# RS485_tranceiver.net
KiCad netlist of a schematic drawn in Altium Designer
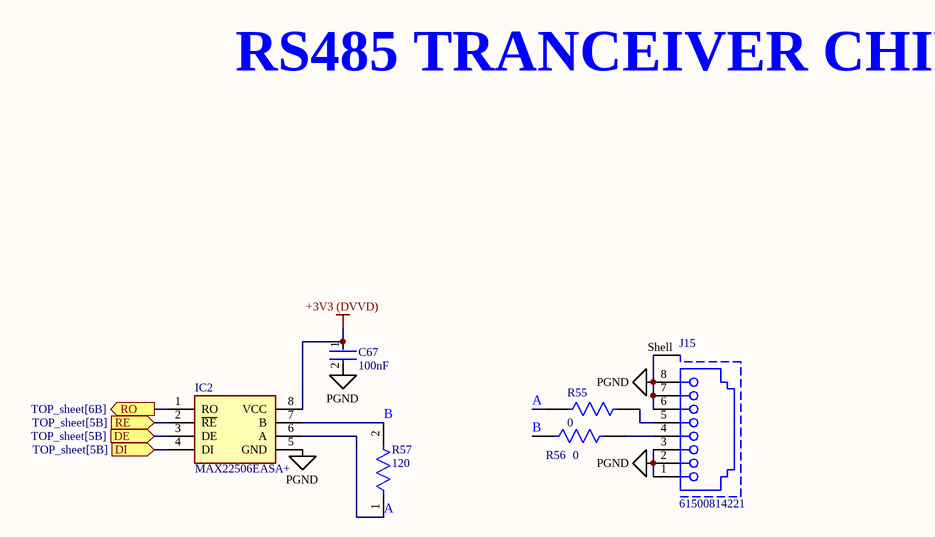
[diagram p0: RS485_tranceiver.SchDoc]

(export (version "E")
  (design (tool "Eeschema 10.0.6"))
  (components
    (comp (ref "C67")
      (value "100nF")
      (footprint "FP-GRM15-MFG")
      (description "CAP CER 0.1UF 16V X7R 0402")
      (fields (field (name "MANUFACTURER PART NUMBER") "GRM155R71C104KA88D") (field (name "TOLERANCE") "10%"))
      (libsource (lib "Altium Content Vault") (part "236180d848d6139a670b325ea6854c9"))
    )
    (comp (ref "IC2")
      (value "MAX22506EASA+")
      (footprint "SamacSys:SOIC127P600X175-8N")
      (description "Integrated Circuit")
      (fields (field (name "MOUSER PART NUMBER") "700-MAX22506EASA+"))
      (libsource (lib "*") (part "MAX22506EASA+"))
    )
    (comp (ref "J15")
      (value "61500814221")
      (footprint "61500814221")
      (libsource (lib "Altium Content Vault") (part "8P8C - 1 Port - Shielded"))
    )
    (comp (ref "R55")
      (value "0")
      (footprint "FP-CRCW1206-MFG")
      (description "CRCW12060000ZSTA Zero Ohm Resistor, Jumper, 1206 [3216 Metric], Thick Film, 250 mW, Surface Mount")
      (libsource (lib "") (part "1029c3af85768c4190bb7ad29bc67b5_1"))
    )
    (comp (ref "R56")
      (value "0")
      (footprint "FP-CRCW1206-MFG")
      (description "CRCW12060000ZSTA Zero Ohm Resistor, Jumper, 1206 [3216 Metric], Thick Film, 250 mW, Surface Mount")
      (libsource (lib "") (part "1029c3af85768c4190bb7ad29bc67b5_1"))
    )
    (comp (ref "R57")
      (value "120")
      (footprint "FP-CRCW1206-MFG")
      (description "CRCW12060000ZS120 Ohm Resistor, Jumper, 1206 [3216 Metric], Thick Film, 250 mW, Surface Mount")
      (libsource (lib "Altium Content Vault") (part "1029c3af85768c4190bb7ad29bc67b5"))
    )
  )
  (nets
    (net (code "1") (name "+3V3 (DVVD)") (class "Default")
      (node (ref "C67") (pin "1") (pinfunction "1_1") (pintype "passive"))
      (node (ref "IC2") (pin "8") (pinfunction "VCC_8") (pintype "passive"))
    )
    (net (code "2") (name "/A") (class "Default")
      (node (ref "IC2") (pin "6") (pinfunction "A_6") (pintype "passive"))
      (node (ref "R55") (pin "1") (pinfunction "1_1") (pintype "passive"))
      (node (ref "R57") (pin "1") (pinfunction "1_1") (pintype "passive"))
    )
    (net (code "3") (name "/B") (class "Default")
      (node (ref "IC2") (pin "7") (pinfunction "B_7") (pintype "passive"))
      (node (ref "R56") (pin "1") (pinfunction "1_1") (pintype "passive"))
      (node (ref "R57") (pin "2") (pinfunction "2_2") (pintype "passive"))
    )
    (net (code "4") (name "/DE") (class "Default")
      (node (ref "IC2") (pin "3") (pinfunction "DE_3") (pintype "passive"))
    )
    (net (code "5") (name "/DI") (class "Default")
      (node (ref "IC2") (pin "4") (pinfunction "DI_4") (pintype "passive"))
    )
    (net (code "6") (name "/RE") (class "Default")
      (node (ref "IC2") (pin "2") (pinfunction "~{RE}_2") (pintype "passive"))
    )
    (net (code "7") (name "/RO") (class "Default")
      (node (ref "IC2") (pin "1") (pinfunction "RO_1") (pintype "passive"))
    )
    (net (code "8") (name "Net-(J15-Pad4)") (class "Default")
      (node (ref "J15") (pin "4") (pinfunction "4_4") (pintype "passive"))
      (node (ref "R56") (pin "2") (pinfunction "2_2") (pintype "passive"))
    )
    (net (code "9") (name "Net-(J15-Pad5)") (class "Default")
      (node (ref "J15") (pin "5") (pinfunction "5_5") (pintype "passive"))
      (node (ref "R55") (pin "2") (pinfunction "2_2") (pintype "passive"))
    )
    (net (code "10") (name "PGND") (class "Default")
      (node (ref "C67") (pin "2") (pinfunction "2_2") (pintype "passive"))
      (node (ref "IC2") (pin "5") (pinfunction "GND_5") (pintype "passive"))
      (node (ref "J15") (pin "1") (pinfunction "1_1") (pintype "passive"))
      (node (ref "J15") (pin "2") (pinfunction "2_2") (pintype "passive"))
      (node (ref "J15") (pin "3") (pinfunction "3_3") (pintype "passive"))
      (node (ref "J15") (pin "6") (pinfunction "6_6") (pintype "passive"))
      (node (ref "J15") (pin "7") (pinfunction "7_7") (pintype "passive"))
      (node (ref "J15") (pin "8") (pinfunction "8_8") (pintype "passive"))
      (node (ref "J15") (pin "Shell") (pinfunction "Shell_Shell") (pintype "passive"))
    )
  )
)
